# Backpanel_GigIO.net
KiCad netlist of a schematic drawn in Altium Designer
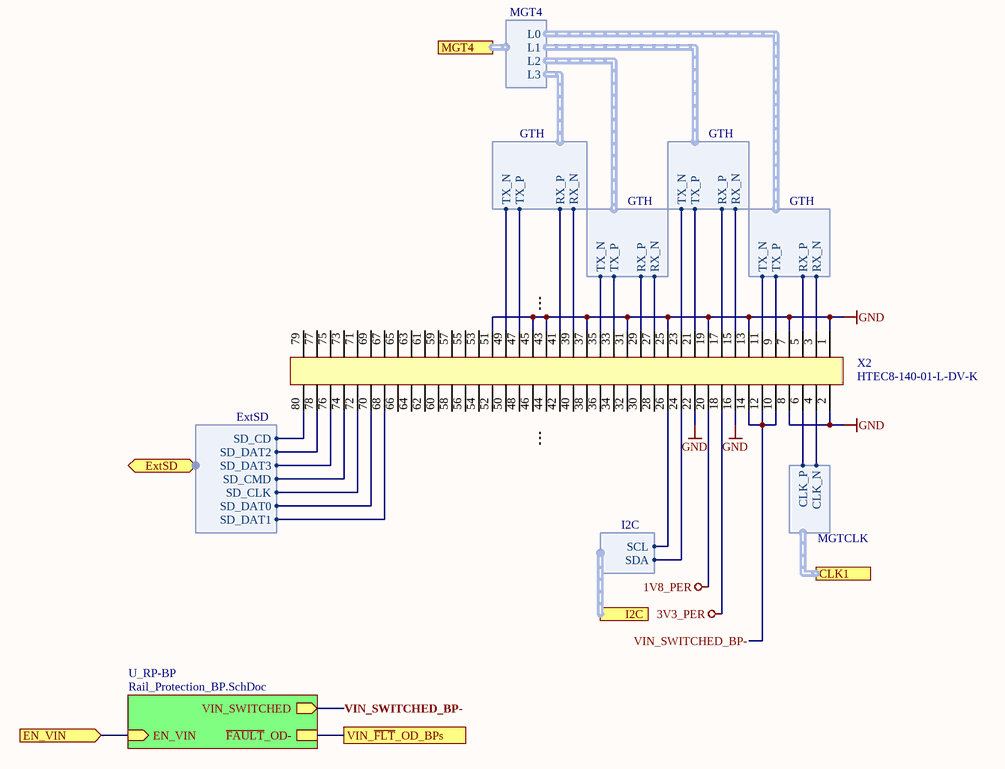
[diagram p0: Backpanel_GigIO.SchDoc]

(export (version "E")
  (design (tool "Eeschema 10.0.6"))
  (components
    (comp (ref "X2")
      (value "HTEC8-140-01-L-DV-K")
      (footprint "HTEC8-140-XX-X-DV")
      (description "Headers & Wire Housings 0.80 mm Rugged High-Speed Edge Card Connectors")
      (fields
        (field (name "MANUFACTURER") "SAMTEC")
        (field (name "LCSC PART NUMBER") "C20365608")
        (field (name "CREATED FROM") "AGeiger")
      )
      (libsource (lib "user") (part "HTEC8-140-01-L-DV-K"))
    )
  )
  (nets
    (net (code "6") (name "/CLK_N") (class "Default")
      (node (ref "X2") (pin "4") (pinfunction "4_4") (pintype "passive"))
    )
    (net (code "7") (name "/CLK_P") (class "Default")
      (node (ref "X2") (pin "6") (pinfunction "6_6") (pintype "passive"))
    )
    (net (code "10") (name "/SCL") (class "Default")
      (node (ref "X2") (pin "26") (pinfunction "26_26") (pintype "passive"))
    )
    (net (code "11") (name "/SDA") (class "Default")
      (node (ref "X2") (pin "24") (pinfunction "24_24") (pintype "passive"))
    )
    (net (code "12") (name "/SD_CD") (class "Default")
      (node (ref "X2") (pin "80") (pinfunction "80_80") (pintype "passive"))
    )
    (net (code "13") (name "/SD_CLK") (class "Default")
      (node (ref "X2") (pin "72") (pinfunction "72_72") (pintype "passive"))
    )
    (net (code "14") (name "/SD_CMD") (class "Default")
      (node (ref "X2") (pin "74") (pinfunction "74_74") (pintype "passive"))
    )
    (net (code "15") (name "/SD_DAT0") (class "Default")
      (node (ref "X2") (pin "70") (pinfunction "70_70") (pintype "passive"))
    )
    (net (code "16") (name "/SD_DAT1") (class "Default")
      (node (ref "X2") (pin "68") (pinfunction "68_68") (pintype "passive"))
    )
    (net (code "17") (name "/SD_DAT2") (class "Default")
      (node (ref "X2") (pin "78") (pinfunction "78_78") (pintype "passive"))
    )
    (net (code "18") (name "/SD_DAT3") (class "Default")
      (node (ref "X2") (pin "76") (pinfunction "76_76") (pintype "passive"))
    )
    (net (code "19") (name "/VIN_SWITCHED_BP-") (class "Default")
      (node (ref "X2") (pin "10") (pinfunction "10_10") (pintype "passive"))
      (node (ref "X2") (pin "12") (pinfunction "12_12") (pintype "passive"))
      (node (ref "X2") (pin "14") (pinfunction "14_14") (pintype "passive"))
    )
    (net (code "25") (name "1V8_PER") (class "Default")
      (node (ref "X2") (pin "20") (pinfunction "20_20") (pintype "passive"))
    )
    (net (code "26") (name "3V3_PER") (class "Default")
      (node (ref "X2") (pin "18") (pinfunction "18_18") (pintype "passive"))
    )
    (net (code "27") (name "GND") (class "Default")
      (node (ref "X2") (pin "1") (pinfunction "1_1") (pintype "passive"))
      (node (ref "X2") (pin "13") (pinfunction "13_13") (pintype "passive"))
      (node (ref "X2") (pin "16") (pinfunction "16_16") (pintype "passive"))
      (node (ref "X2") (pin "19") (pinfunction "19_19") (pintype "passive"))
      (node (ref "X2") (pin "2") (pinfunction "2_2") (pintype "passive"))
      (node (ref "X2") (pin "22") (pinfunction "22_22") (pintype "passive"))
      (node (ref "X2") (pin "25") (pinfunction "25_25") (pintype "passive"))
      (node (ref "X2") (pin "31") (pinfunction "31_31") (pintype "passive"))
      (node (ref "X2") (pin "37") (pinfunction "37_37") (pintype "passive"))
      (node (ref "X2") (pin "43") (pinfunction "43_43") (pintype "passive"))
      (node (ref "X2") (pin "45") (pinfunction "45_45") (pintype "passive"))
      (node (ref "X2") (pin "51") (pinfunction "51_51") (pintype "passive"))
      (node (ref "X2") (pin "7") (pinfunction "7_7") (pintype "passive"))
      (node (ref "X2") (pin "8") (pinfunction "8_8") (pintype "passive"))
    )
    (net (code "28") (name "unconnected-(X2-Pad3)") (class "Default")
      (node (ref "X2") (pin "3") (pinfunction "3_3") (pintype "passive"))
    )
    (net (code "29") (name "unconnected-(X2-Pad5)") (class "Default")
      (node (ref "X2") (pin "5") (pinfunction "5_5") (pintype "passive"))
    )
    (net (code "30") (name "unconnected-(X2-Pad9)") (class "Default")
      (node (ref "X2") (pin "9") (pinfunction "9_9") (pintype "passive"))
    )
    (net (code "31") (name "unconnected-(X2-Pad11)") (class "Default")
      (node (ref "X2") (pin "11") (pinfunction "11_11") (pintype "passive"))
    )
    (net (code "32") (name "unconnected-(X2-Pad15)") (class "Default")
      (node (ref "X2") (pin "15") (pinfunction "15_15") (pintype "passive"))
    )
    (net (code "33") (name "unconnected-(X2-Pad17)") (class "Default")
      (node (ref "X2") (pin "17") (pinfunction "17_17") (pintype "passive"))
    )
    (net (code "34") (name "unconnected-(X2-Pad21)") (class "Default")
      (node (ref "X2") (pin "21") (pinfunction "21_21") (pintype "passive"))
    )
    (net (code "35") (name "unconnected-(X2-Pad23)") (class "Default")
      (node (ref "X2") (pin "23") (pinfunction "23_23") (pintype "passive"))
    )
    (net (code "36") (name "unconnected-(X2-Pad27)") (class "Default")
      (node (ref "X2") (pin "27") (pinfunction "27_27") (pintype "passive"))
    )
    (net (code "37") (name "unconnected-(X2-Pad28)") (class "Default")
      (node (ref "X2") (pin "28") (pinfunction "28_28") (pintype "passive"))
    )
    (net (code "38") (name "unconnected-(X2-Pad29)") (class "Default")
      (node (ref "X2") (pin "29") (pinfunction "29_29") (pintype "passive"))
    )
    (net (code "39") (name "unconnected-(X2-Pad30)") (class "Default")
      (node (ref "X2") (pin "30") (pinfunction "30_30") (pintype "passive"))
    )
    (net (code "40") (name "unconnected-(X2-Pad32)") (class "Default")
      (node (ref "X2") (pin "32") (pinfunction "32_32") (pintype "passive"))
    )
    (net (code "41") (name "unconnected-(X2-Pad33)") (class "Default")
      (node (ref "X2") (pin "33") (pinfunction "33_33") (pintype "passive"))
    )
    (net (code "42") (name "unconnected-(X2-Pad34)") (class "Default")
      (node (ref "X2") (pin "34") (pinfunction "34_34") (pintype "passive"))
    )
    (net (code "43") (name "unconnected-(X2-Pad35)") (class "Default")
      (node (ref "X2") (pin "35") (pinfunction "35_35") (pintype "passive"))
    )
    (net (code "44") (name "unconnected-(X2-Pad36)") (class "Default")
      (node (ref "X2") (pin "36") (pinfunction "36_36") (pintype "passive"))
    )
    (net (code "45") (name "unconnected-(X2-Pad38)") (class "Default")
      (node (ref "X2") (pin "38") (pinfunction "38_38") (pintype "passive"))
    )
    (net (code "46") (name "unconnected-(X2-Pad39)") (class "Default")
      (node (ref "X2") (pin "39") (pinfunction "39_39") (pintype "passive"))
    )
    (net (code "47") (name "unconnected-(X2-Pad40)") (class "Default")
      (node (ref "X2") (pin "40") (pinfunction "40_40") (pintype "passive"))
    )
    (net (code "48") (name "unconnected-(X2-Pad41)") (class "Default")
      (node (ref "X2") (pin "41") (pinfunction "41_41") (pintype "passive"))
    )
    (net (code "49") (name "unconnected-(X2-Pad42)") (class "Default")
      (node (ref "X2") (pin "42") (pinfunction "42_42") (pintype "passive"))
    )
    (net (code "50") (name "unconnected-(X2-Pad44)") (class "Default")
      (node (ref "X2") (pin "44") (pinfunction "44_44") (pintype "passive"))
    )
    (net (code "51") (name "unconnected-(X2-Pad46)") (class "Default")
      (node (ref "X2") (pin "46") (pinfunction "46_46") (pintype "passive"))
    )
    (net (code "52") (name "unconnected-(X2-Pad47)") (class "Default")
      (node (ref "X2") (pin "47") (pinfunction "47_47") (pintype "passive"))
    )
    (net (code "53") (name "unconnected-(X2-Pad48)") (class "Default")
      (node (ref "X2") (pin "48") (pinfunction "48_48") (pintype "passive"))
    )
    (net (code "54") (name "unconnected-(X2-Pad49)") (class "Default")
      (node (ref "X2") (pin "49") (pinfunction "49_49") (pintype "passive"))
    )
    (net (code "55") (name "unconnected-(X2-Pad50)") (class "Default")
      (node (ref "X2") (pin "50") (pinfunction "50_50") (pintype "passive"))
    )
    (net (code "56") (name "unconnected-(X2-Pad52)") (class "Default")
      (node (ref "X2") (pin "52") (pinfunction "52_52") (pintype "passive"))
    )
    (net (code "57") (name "unconnected-(X2-Pad53)") (class "Default")
      (node (ref "X2") (pin "53") (pinfunction "53_53") (pintype "passive"))
    )
    (net (code "58") (name "unconnected-(X2-Pad54)") (class "Default")
      (node (ref "X2") (pin "54") (pinfunction "54_54") (pintype "passive"))
    )
    (net (code "59") (name "unconnected-(X2-Pad55)") (class "Default")
      (node (ref "X2") (pin "55") (pinfunction "55_55") (pintype "passive"))
    )
    (net (code "60") (name "unconnected-(X2-Pad56)") (class "Default")
      (node (ref "X2") (pin "56") (pinfunction "56_56") (pintype "passive"))
    )
    (net (code "61") (name "unconnected-(X2-Pad57)") (class "Default")
      (node (ref "X2") (pin "57") (pinfunction "57_57") (pintype "passive"))
    )
    (net (code "62") (name "unconnected-(X2-Pad58)") (class "Default")
      (node (ref "X2") (pin "58") (pinfunction "58_58") (pintype "passive"))
    )
    (net (code "63") (name "unconnected-(X2-Pad59)") (class "Default")
      (node (ref "X2") (pin "59") (pinfunction "59_59") (pintype "passive"))
    )
    (net (code "64") (name "unconnected-(X2-Pad60)") (class "Default")
      (node (ref "X2") (pin "60") (pinfunction "60_60") (pintype "passive"))
    )
    (net (code "65") (name "unconnected-(X2-Pad61)") (class "Default")
      (node (ref "X2") (pin "61") (pinfunction "61_61") (pintype "passive"))
    )
    (net (code "66") (name "unconnected-(X2-Pad62)") (class "Default")
      (node (ref "X2") (pin "62") (pinfunction "62_62") (pintype "passive"))
    )
    (net (code "67") (name "unconnected-(X2-Pad63)") (class "Default")
      (node (ref "X2") (pin "63") (pinfunction "63_63") (pintype "passive"))
    )
    (net (code "68") (name "unconnected-(X2-Pad64)") (class "Default")
      (node (ref "X2") (pin "64") (pinfunction "64_64") (pintype "passive"))
    )
    (net (code "69") (name "unconnected-(X2-Pad65)") (class "Default")
      (node (ref "X2") (pin "65") (pinfunction "65_65") (pintype "passive"))
    )
    (net (code "70") (name "unconnected-(X2-Pad66)") (class "Default")
      (node (ref "X2") (pin "66") (pinfunction "66_66") (pintype "passive"))
    )
    (net (code "71") (name "unconnected-(X2-Pad67)") (class "Default")
      (node (ref "X2") (pin "67") (pinfunction "67_67") (pintype "passive"))
    )
    (net (code "72") (name "unconnected-(X2-Pad69)") (class "Default")
      (node (ref "X2") (pin "69") (pinfunction "69_69") (pintype "passive"))
    )
    (net (code "73") (name "unconnected-(X2-Pad71)") (class "Default")
      (node (ref "X2") (pin "71") (pinfunction "71_71") (pintype "passive"))
    )
    (net (code "74") (name "unconnected-(X2-Pad73)") (class "Default")
      (node (ref "X2") (pin "73") (pinfunction "73_73") (pintype "passive"))
    )
    (net (code "75") (name "unconnected-(X2-Pad75)") (class "Default")
      (node (ref "X2") (pin "75") (pinfunction "75_75") (pintype "passive"))
    )
    (net (code "76") (name "unconnected-(X2-Pad77)") (class "Default")
      (node (ref "X2") (pin "77") (pinfunction "77_77") (pintype "passive"))
    )
    (net (code "77") (name "unconnected-(X2-Pad79)") (class "Default")
      (node (ref "X2") (pin "79") (pinfunction "79_79") (pintype "passive"))
    )
  )
)
